# cyberspace-1-ram-rom-card.net
KiCad netlist of a schematic drawn in EAGLE
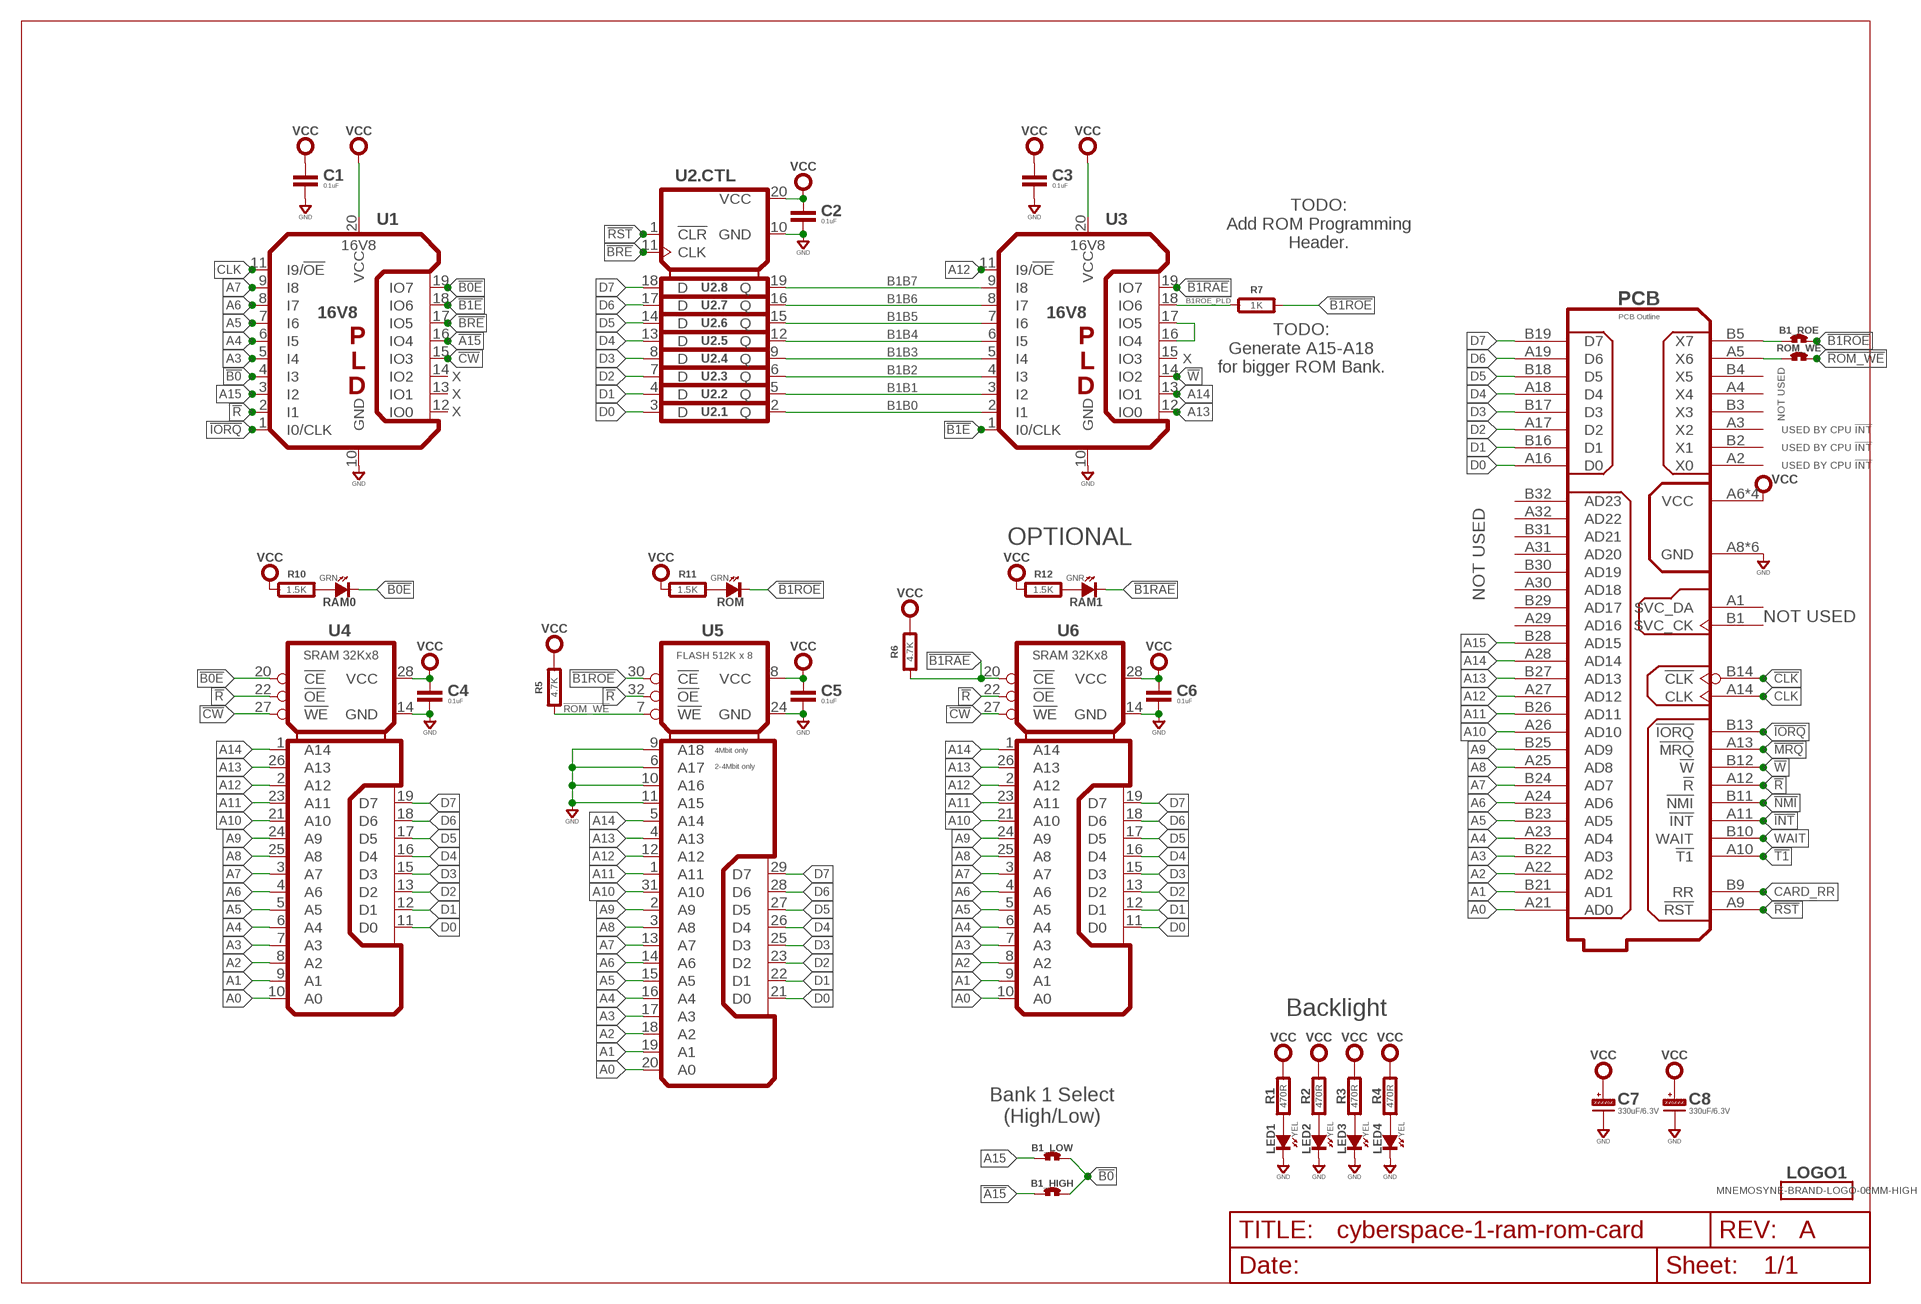
[diagram p0: schematic, sheet 1]

(export (version "E")
  (design (tool "Eeschema 10.0.6"))
  (components
    (comp (ref "B1_HIGH")
      (value "SOLDER_JUMPER-60MIL-RND")
      (footprint "eagle-import:SOLDER_JUMP_60MIL_RND")
      (libsource (lib "eagle-import") (part "SOLDER_JUMPER-60MIL-RND"))
    )
    (comp (ref "B1_LOW")
      (value "SOLDER_JUMPER-60MIL-RND")
      (footprint "eagle-import:SOLDER_JUMP_60MIL_RND")
      (libsource (lib "eagle-import") (part "SOLDER_JUMPER-60MIL-RND"))
    )
    (comp (ref "B1_ROE")
      (value "SOLDER_JUMPER-60MIL-RND")
      (footprint "eagle-import:SOLDER_JUMP_60MIL_RND")
      (libsource (lib "eagle-import") (part "SOLDER_JUMPER-60MIL-RND"))
    )
    (comp (ref "C1")
      (value "0.1uF")
      (footprint "eagle-import:0603-CAP")
      (libsource (lib "eagle-import") (part "CAPACITOR0603"))
    )
    (comp (ref "C2")
      (value "0.1uF")
      (footprint "eagle-import:0603-CAP")
      (libsource (lib "eagle-import") (part "CAPACITOR0603"))
    )
    (comp (ref "C3")
      (value "0.1uF")
      (footprint "eagle-import:0603-CAP")
      (libsource (lib "eagle-import") (part "CAPACITOR0603"))
    )
    (comp (ref "C4")
      (value "0.1uF")
      (footprint "eagle-import:0603-CAP")
      (libsource (lib "eagle-import") (part "CAPACITOR0603"))
    )
    (comp (ref "C5")
      (value "0.1uF")
      (footprint "eagle-import:0603-CAP")
      (libsource (lib "eagle-import") (part "CAPACITOR0603"))
    )
    (comp (ref "C6")
      (value "0.1uF")
      (footprint "eagle-import:0603-CAP")
      (libsource (lib "eagle-import") (part "CAPACITOR0603"))
    )
    (comp (ref "C7")
      (value "330uF/6.3V")
      (footprint "eagle-import:CAP_ALUM_SMT_6.3")
      (libsource (lib "eagle-import") (part "CAPACITOR_POL-ALUM-SMT-6.3"))
    )
    (comp (ref "C8")
      (value "330uF/6.3V")
      (footprint "eagle-import:CAP_ALUM_SMT_6.3")
      (libsource (lib "eagle-import") (part "CAPACITOR_POL-ALUM-SMT-6.3"))
    )
    (comp (ref "LED1")
      (value "YEL")
      (footprint "eagle-import:SMD_0603")
      (libsource (lib "eagle-import") (part "SMT0603"))
    )
    (comp (ref "LED2")
      (value "YEL")
      (footprint "eagle-import:SMD_0603")
      (libsource (lib "eagle-import") (part "SMT0603"))
    )
    (comp (ref "LED3")
      (value "YEL")
      (footprint "eagle-import:SMD_0603")
      (libsource (lib "eagle-import") (part "SMT0603"))
    )
    (comp (ref "LED4")
      (value "YEL")
      (footprint "eagle-import:SMD_0603")
      (libsource (lib "eagle-import") (part "SMT0603"))
    )
    (comp (ref "LOGO1")
      (value "MNEMOSYNE-BRAND-LOGO-06MM-HIGH")
      (footprint "eagle-import:MNEMOSYNE-06MM")
      (libsource (lib "eagle-import") (part "MNEMOSYNE-BRAND-LOGO-06MM-HIGH"))
    )
    (comp (ref "PCB")
      (value "PCB Outline")
      (footprint "eagle-import:CYBERSPACE-CARD-TYPE-1A")
      (libsource (lib "eagle-import") (part "CYBERSPACE-1-CARD-1A"))
    )
    (comp (ref "R1")
      (value "470R")
      (footprint "eagle-import:0603-RES")
      (libsource (lib "eagle-import") (part "RESISTOR0603"))
    )
    (comp (ref "R2")
      (value "470R")
      (footprint "eagle-import:0603-RES")
      (libsource (lib "eagle-import") (part "RESISTOR0603"))
    )
    (comp (ref "R3")
      (value "470R")
      (footprint "eagle-import:0603-RES")
      (libsource (lib "eagle-import") (part "RESISTOR0603"))
    )
    (comp (ref "R4")
      (value "470R")
      (footprint "eagle-import:0603-RES")
      (libsource (lib "eagle-import") (part "RESISTOR0603"))
    )
    (comp (ref "R5")
      (value "4.7K")
      (footprint "eagle-import:0603-RES")
      (libsource (lib "eagle-import") (part "RESISTOR0603"))
    )
    (comp (ref "R6")
      (value "4.7K")
      (footprint "eagle-import:0603-RES")
      (libsource (lib "eagle-import") (part "RESISTOR0603"))
    )
    (comp (ref "R7")
      (value "1K")
      (footprint "eagle-import:0603-RES")
      (libsource (lib "eagle-import") (part "RESISTOR0603"))
    )
    (comp (ref "R10")
      (value "1.5K")
      (footprint "eagle-import:0603-RES")
      (libsource (lib "eagle-import") (part "RESISTOR0603"))
    )
    (comp (ref "R11")
      (value "1.5K")
      (footprint "eagle-import:0603-RES")
      (libsource (lib "eagle-import") (part "RESISTOR0603"))
    )
    (comp (ref "R12")
      (value "1.5K")
      (footprint "eagle-import:0603-RES")
      (libsource (lib "eagle-import") (part "RESISTOR0603"))
    )
    (comp (ref "RAM0")
      (value "GRN")
      (footprint "eagle-import:SMD_0603")
      (libsource (lib "eagle-import") (part "SMT0603"))
    )
    (comp (ref "RAM1")
      (value "GNR")
      (footprint "eagle-import:SMD_0603")
      (libsource (lib "eagle-import") (part "SMT0603"))
    )
    (comp (ref "ROM")
      (value "GRN")
      (footprint "eagle-import:SMD_0603")
      (libsource (lib "eagle-import") (part "SMT0603"))
    )
    (comp (ref "ROM_WE")
      (value "SOLDER_JUMPER-60MIL-RND")
      (footprint "eagle-import:SOLDER_JUMP_60MIL_RND")
      (libsource (lib "eagle-import") (part "SOLDER_JUMPER-60MIL-RND"))
    )
    (comp (ref "U1")
      (value "16V8")
      (footprint "eagle-import:SOP20")
      (fields (field (name "MFR") "Atmel") (field (name "MPN") "AF16V8B15SU"))
      (libsource (lib "eagle-import") (part "16V8-SOIC"))
    )
    (comp (ref "U2")
      (value "74AHCT273NS")
      (footprint "eagle-import:SO20")
      (libsource (lib "eagle-import") (part "74273?NSAHCT"))
    )
    (comp (ref "U3")
      (value "16V8")
      (footprint "eagle-import:SOP20")
      (fields (field (name "MFR") "Atmel") (field (name "MPN") "AF16V8B15SU"))
      (libsource (lib "eagle-import") (part "16V8-SOIC"))
    )
    (comp (ref "U4")
      (value "SRAM 32Kx8")
      (footprint "eagle-import:SOP28-330W")
      (fields (field (name "MFR") "ISSI") (field (name "MPN") "IS62C256AL-45UL"))
      (libsource (lib "eagle-import") (part "62256ULC"))
    )
    (comp (ref "U5")
      (value "FLASH 512K x 8")
      (footprint "eagle-import:TSOP32-14X8MM")
      (fields (field (name "MFR") "Microchip") (field (name "MPN") "SST39SF040-70-4C-Wxx"))
      (libsource (lib "eagle-import") (part "FLASH_512KX8-512K-TSOP"))
    )
    (comp (ref "U6")
      (value "SRAM 32Kx8")
      (footprint "eagle-import:SOP28-330W")
      (fields (field (name "MFR") "ISSI") (field (name "MPN") "IS62C256AL-45UL"))
      (libsource (lib "eagle-import") (part "62256ULC"))
    )
  )
  (nets
    (net (code "1") (name "/B1B0") (class "Default")
      (node (ref "U2") (pin "2") (pinfunction "Q_2") (pintype "output"))
      (node (ref "U3") (pin "2") (pinfunction "I1_2") (pintype "bidirectional"))
    )
    (net (code "2") (name "/B1B1") (class "Default")
      (node (ref "U2") (pin "5") (pinfunction "Q_5") (pintype "output"))
      (node (ref "U3") (pin "3") (pinfunction "I2_3") (pintype "bidirectional"))
    )
    (net (code "3") (name "/B1B2") (class "Default")
      (node (ref "U2") (pin "6") (pinfunction "Q_6") (pintype "output"))
      (node (ref "U3") (pin "4") (pinfunction "I3_4") (pintype "bidirectional"))
    )
    (net (code "4") (name "/B1B3") (class "Default")
      (node (ref "U2") (pin "9") (pinfunction "Q_9") (pintype "output"))
      (node (ref "U3") (pin "5") (pinfunction "I4_5") (pintype "bidirectional"))
    )
    (net (code "5") (name "/B1B4") (class "Default")
      (node (ref "U2") (pin "12") (pinfunction "Q_12") (pintype "output"))
      (node (ref "U3") (pin "6") (pinfunction "I5_6") (pintype "bidirectional"))
    )
    (net (code "6") (name "/B1B5") (class "Default")
      (node (ref "U2") (pin "15") (pinfunction "Q_15") (pintype "output"))
      (node (ref "U3") (pin "7") (pinfunction "I6_7") (pintype "bidirectional"))
    )
    (net (code "7") (name "/B1B6") (class "Default")
      (node (ref "U2") (pin "16") (pinfunction "Q_16") (pintype "output"))
      (node (ref "U3") (pin "8") (pinfunction "I7_8") (pintype "bidirectional"))
    )
    (net (code "8") (name "/B1B7") (class "Default")
      (node (ref "U2") (pin "19") (pinfunction "Q_19") (pintype "output"))
      (node (ref "U3") (pin "9") (pinfunction "I8_9") (pintype "bidirectional"))
    )
    (net (code "9") (name "/~{A15}") (class "Default")
      (node (ref "B1_HIGH") (pin "1") (pinfunction "P$1_1") (pintype "passive"))
      (node (ref "U1") (pin "16") (pinfunction "IO4_16") (pintype "bidirectional"))
    )
    (net (code "10") (name "/~{B0E}") (class "Default")
      (node (ref "RAM0") (pin "K") (pinfunction "C_K") (pintype "passive"))
      (node (ref "U1") (pin "19") (pinfunction "IO7_19") (pintype "bidirectional"))
      (node (ref "U4") (pin "20") (pinfunction "~{CE}_20") (pintype "input"))
    )
    (net (code "11") (name "/~{B0}") (class "Default")
      (node (ref "B1_HIGH") (pin "2") (pinfunction "P$2_2") (pintype "passive"))
      (node (ref "B1_LOW") (pin "2") (pinfunction "P$2_2") (pintype "passive"))
      (node (ref "U1") (pin "4") (pinfunction "I3_4") (pintype "bidirectional"))
    )
    (net (code "12") (name "/~{B1E}") (class "Default")
      (node (ref "U1") (pin "18") (pinfunction "IO6_18") (pintype "bidirectional"))
      (node (ref "U3") (pin "1") (pinfunction "I0/CLK_1") (pintype "bidirectional"))
    )
    (net (code "13") (name "/~{B1RAE}") (class "Default")
      (node (ref "R6") (pin "1") (pinfunction "1_1") (pintype "passive"))
      (node (ref "RAM1") (pin "K") (pinfunction "C_K") (pintype "passive"))
      (node (ref "U3") (pin "19") (pinfunction "IO7_19") (pintype "bidirectional"))
      (node (ref "U6") (pin "20") (pinfunction "~{CE}_20") (pintype "input"))
    )
    (net (code "14") (name "/~{B1ROE_PLD}") (class "Default")
      (node (ref "R7") (pin "1") (pinfunction "1_1") (pintype "passive"))
      (node (ref "U3") (pin "18") (pinfunction "IO6_18") (pintype "bidirectional"))
    )
    (net (code "15") (name "/~{B1ROE}") (class "Default")
      (node (ref "B1_ROE") (pin "2") (pinfunction "P$2_2") (pintype "passive"))
      (node (ref "R7") (pin "2") (pinfunction "2_2") (pintype "passive"))
      (node (ref "ROM") (pin "K") (pinfunction "C_K") (pintype "passive"))
      (node (ref "U5") (pin "30") (pinfunction "~{CE}_30") (pintype "input"))
    )
    (net (code "16") (name "/~{BRE}") (class "Default")
      (node (ref "U1") (pin "17") (pinfunction "IO5_17") (pintype "bidirectional"))
      (node (ref "U2") (pin "11") (pinfunction "CLK_11") (pintype "input"))
    )
    (net (code "17") (name "/~{CLK}") (class "Default")
      (node (ref "PCB") (pin "B14") (pinfunction "~{CLK}_B14") (pintype "bidirectional"))
    )
    (net (code "18") (name "/~{CW}") (class "Default")
      (node (ref "U1") (pin "15") (pinfunction "IO3_15") (pintype "bidirectional"))
      (node (ref "U4") (pin "27") (pinfunction "~{WE}_27") (pintype "input"))
      (node (ref "U6") (pin "27") (pinfunction "~{WE}_27") (pintype "input"))
    )
    (net (code "19") (name "/~{INT}") (class "Default")
      (node (ref "PCB") (pin "A11") (pinfunction "~{INT}_A11") (pintype "bidirectional"))
    )
    (net (code "20") (name "/~{IORQ}") (class "Default")
      (node (ref "PCB") (pin "B13") (pinfunction "~{IORQ}_B13") (pintype "bidirectional"))
      (node (ref "U1") (pin "1") (pinfunction "I0/CLK_1") (pintype "bidirectional"))
    )
    (net (code "21") (name "/~{MRQ}") (class "Default")
      (node (ref "PCB") (pin "A13") (pinfunction "~{MRQ}_A13") (pintype "bidirectional"))
    )
    (net (code "22") (name "/~{NMI}") (class "Default")
      (node (ref "PCB") (pin "B11") (pinfunction "~{NMI}_B11") (pintype "bidirectional"))
    )
    (net (code "23") (name "/~{ROM_WE}") (class "Default")
      (node (ref "R5") (pin "1") (pinfunction "1_1") (pintype "passive"))
      (node (ref "ROM_WE") (pin "2") (pinfunction "P$2_2") (pintype "passive"))
      (node (ref "U5") (pin "7") (pinfunction "~{WE}_7") (pintype "input"))
    )
    (net (code "24") (name "/~{RST}") (class "Default")
      (node (ref "PCB") (pin "A9") (pinfunction "~{RST}_A9") (pintype "bidirectional"))
      (node (ref "U2") (pin "1") (pinfunction "~{CLR}_1") (pintype "input"))
    )
    (net (code "25") (name "/~{R}") (class "Default")
      (node (ref "PCB") (pin "A12") (pinfunction "~{R}_A12") (pintype "bidirectional"))
      (node (ref "U1") (pin "2") (pinfunction "I1_2") (pintype "bidirectional"))
      (node (ref "U4") (pin "22") (pinfunction "~{OE}_22") (pintype "input"))
      (node (ref "U5") (pin "32") (pinfunction "~{OE}_32") (pintype "input"))
      (node (ref "U6") (pin "22") (pinfunction "~{OE}_22") (pintype "input"))
    )
    (net (code "26") (name "/~{T1}") (class "Default")
      (node (ref "PCB") (pin "A10") (pinfunction "~{T1}_A10") (pintype "bidirectional"))
    )
    (net (code "27") (name "/~{W}") (class "Default")
      (node (ref "PCB") (pin "B12") (pinfunction "~{W}_B12") (pintype "bidirectional"))
      (node (ref "U3") (pin "14") (pinfunction "IO2_14") (pintype "bidirectional"))
    )
    (net (code "28") (name "A0") (class "Default")
      (node (ref "PCB") (pin "A21") (pinfunction "AD0_A21") (pintype "bidirectional"))
      (node (ref "U4") (pin "10") (pinfunction "A0_10") (pintype "input"))
      (node (ref "U5") (pin "20") (pinfunction "A0_20") (pintype "input"))
      (node (ref "U6") (pin "10") (pinfunction "A0_10") (pintype "input"))
    )
    (net (code "29") (name "A1") (class "Default")
      (node (ref "PCB") (pin "B21") (pinfunction "AD1_B21") (pintype "bidirectional"))
      (node (ref "U4") (pin "9") (pinfunction "A1_9") (pintype "input"))
      (node (ref "U5") (pin "19") (pinfunction "A1_19") (pintype "input"))
      (node (ref "U6") (pin "9") (pinfunction "A1_9") (pintype "input"))
    )
    (net (code "30") (name "A2") (class "Default")
      (node (ref "PCB") (pin "A22") (pinfunction "AD2_A22") (pintype "bidirectional"))
      (node (ref "U4") (pin "8") (pinfunction "A2_8") (pintype "input"))
      (node (ref "U5") (pin "18") (pinfunction "A2_18") (pintype "input"))
      (node (ref "U6") (pin "8") (pinfunction "A2_8") (pintype "input"))
    )
    (net (code "31") (name "A3") (class "Default")
      (node (ref "PCB") (pin "B22") (pinfunction "AD3_B22") (pintype "bidirectional"))
      (node (ref "U1") (pin "5") (pinfunction "I4_5") (pintype "bidirectional"))
      (node (ref "U4") (pin "7") (pinfunction "A3_7") (pintype "input"))
      (node (ref "U5") (pin "17") (pinfunction "A3_17") (pintype "input"))
      (node (ref "U6") (pin "7") (pinfunction "A3_7") (pintype "input"))
    )
    (net (code "32") (name "A4") (class "Default")
      (node (ref "PCB") (pin "A23") (pinfunction "AD4_A23") (pintype "bidirectional"))
      (node (ref "U1") (pin "6") (pinfunction "I5_6") (pintype "bidirectional"))
      (node (ref "U4") (pin "6") (pinfunction "A4_6") (pintype "input"))
      (node (ref "U5") (pin "16") (pinfunction "A4_16") (pintype "input"))
      (node (ref "U6") (pin "6") (pinfunction "A4_6") (pintype "input"))
    )
    (net (code "33") (name "A5") (class "Default")
      (node (ref "PCB") (pin "B23") (pinfunction "AD5_B23") (pintype "bidirectional"))
      (node (ref "U1") (pin "7") (pinfunction "I6_7") (pintype "bidirectional"))
      (node (ref "U4") (pin "5") (pinfunction "A5_5") (pintype "input"))
      (node (ref "U5") (pin "15") (pinfunction "A5_15") (pintype "input"))
      (node (ref "U6") (pin "5") (pinfunction "A5_5") (pintype "input"))
    )
    (net (code "34") (name "A6") (class "Default")
      (node (ref "PCB") (pin "A24") (pinfunction "AD6_A24") (pintype "bidirectional"))
      (node (ref "U1") (pin "8") (pinfunction "I7_8") (pintype "bidirectional"))
      (node (ref "U4") (pin "4") (pinfunction "A6_4") (pintype "input"))
      (node (ref "U5") (pin "14") (pinfunction "A6_14") (pintype "input"))
      (node (ref "U6") (pin "4") (pinfunction "A6_4") (pintype "input"))
    )
    (net (code "35") (name "A7") (class "Default")
      (node (ref "PCB") (pin "B24") (pinfunction "AD7_B24") (pintype "bidirectional"))
      (node (ref "U1") (pin "9") (pinfunction "I8_9") (pintype "bidirectional"))
      (node (ref "U4") (pin "3") (pinfunction "A7_3") (pintype "input"))
      (node (ref "U5") (pin "13") (pinfunction "A7_13") (pintype "input"))
      (node (ref "U6") (pin "3") (pinfunction "A7_3") (pintype "input"))
    )
    (net (code "36") (name "A8") (class "Default")
      (node (ref "PCB") (pin "A25") (pinfunction "AD8_A25") (pintype "bidirectional"))
      (node (ref "U4") (pin "25") (pinfunction "A8_25") (pintype "input"))
      (node (ref "U5") (pin "3") (pinfunction "A8_3") (pintype "input"))
      (node (ref "U6") (pin "25") (pinfunction "A8_25") (pintype "input"))
    )
    (net (code "37") (name "A9") (class "Default")
      (node (ref "PCB") (pin "B25") (pinfunction "AD9_B25") (pintype "bidirectional"))
      (node (ref "U4") (pin "24") (pinfunction "A9_24") (pintype "input"))
      (node (ref "U5") (pin "2") (pinfunction "A9_2") (pintype "input"))
      (node (ref "U6") (pin "24") (pinfunction "A9_24") (pintype "input"))
    )
    (net (code "38") (name "A10") (class "Default")
      (node (ref "PCB") (pin "A26") (pinfunction "AD10_A26") (pintype "bidirectional"))
      (node (ref "U4") (pin "21") (pinfunction "A10_21") (pintype "input"))
      (node (ref "U5") (pin "31") (pinfunction "A10_31") (pintype "input"))
      (node (ref "U6") (pin "21") (pinfunction "A10_21") (pintype "input"))
    )
    (net (code "39") (name "A11") (class "Default")
      (node (ref "PCB") (pin "B26") (pinfunction "AD11_B26") (pintype "bidirectional"))
      (node (ref "U4") (pin "23") (pinfunction "A11_23") (pintype "input"))
      (node (ref "U5") (pin "1") (pinfunction "A11_1") (pintype "input"))
      (node (ref "U6") (pin "23") (pinfunction "A11_23") (pintype "input"))
    )
    (net (code "40") (name "A12") (class "Default")
      (node (ref "PCB") (pin "A27") (pinfunction "AD12_A27") (pintype "bidirectional"))
      (node (ref "U3") (pin "11") (pinfunction "I9/~{OE}_11") (pintype "bidirectional"))
      (node (ref "U4") (pin "2") (pinfunction "A12_2") (pintype "input"))
      (node (ref "U5") (pin "12") (pinfunction "A12_12") (pintype "input"))
      (node (ref "U6") (pin "2") (pinfunction "A12_2") (pintype "input"))
    )
    (net (code "41") (name "A13") (class "Default")
      (node (ref "PCB") (pin "B27") (pinfunction "AD13_B27") (pintype "bidirectional"))
      (node (ref "U3") (pin "12") (pinfunction "IO0_12") (pintype "bidirectional"))
      (node (ref "U4") (pin "26") (pinfunction "A13_26") (pintype "input"))
      (node (ref "U5") (pin "4") (pinfunction "A13_4") (pintype "input"))
      (node (ref "U6") (pin "26") (pinfunction "A13_26") (pintype "input"))
    )
    (net (code "42") (name "A14") (class "Default")
      (node (ref "PCB") (pin "A28") (pinfunction "AD14_A28") (pintype "bidirectional"))
      (node (ref "U3") (pin "13") (pinfunction "IO1_13") (pintype "bidirectional"))
      (node (ref "U4") (pin "1") (pinfunction "A14_1") (pintype "input"))
      (node (ref "U5") (pin "5") (pinfunction "A14_5") (pintype "input"))
      (node (ref "U6") (pin "1") (pinfunction "A14_1") (pintype "input"))
    )
    (net (code "43") (name "A15") (class "Default")
      (node (ref "B1_LOW") (pin "1") (pinfunction "P$1_1") (pintype "passive"))
      (node (ref "PCB") (pin "B28") (pinfunction "AD15_B28") (pintype "bidirectional"))
      (node (ref "U1") (pin "3") (pinfunction "I2_3") (pintype "bidirectional"))
    )
    (net (code "44") (name "CARD_RR") (class "Default")
      (node (ref "PCB") (pin "B9") (pinfunction "RR_B9") (pintype "bidirectional"))
    )
    (net (code "45") (name "CLK") (class "Default")
      (node (ref "PCB") (pin "A14") (pinfunction "CLK_A14") (pintype "bidirectional"))
      (node (ref "U1") (pin "11") (pinfunction "I9/~{OE}_11") (pintype "bidirectional"))
    )
    (net (code "46") (name "D0") (class "Default")
      (node (ref "PCB") (pin "A16") (pinfunction "D0_A16") (pintype "bidirectional"))
      (node (ref "U2") (pin "3") (pinfunction "D_3") (pintype "input"))
      (node (ref "U4") (pin "11") (pinfunction "D0_11") (pintype "bidirectional"))
      (node (ref "U5") (pin "21") (pinfunction "D0_21") (pintype "bidirectional"))
      (node (ref "U6") (pin "11") (pinfunction "D0_11") (pintype "bidirectional"))
    )
    (net (code "47") (name "D1") (class "Default")
      (node (ref "PCB") (pin "B16") (pinfunction "D1_B16") (pintype "bidirectional"))
      (node (ref "U2") (pin "4") (pinfunction "D_4") (pintype "input"))
      (node (ref "U4") (pin "12") (pinfunction "D1_12") (pintype "bidirectional"))
      (node (ref "U5") (pin "22") (pinfunction "D1_22") (pintype "bidirectional"))
      (node (ref "U6") (pin "12") (pinfunction "D1_12") (pintype "bidirectional"))
    )
    (net (code "48") (name "D2") (class "Default")
      (node (ref "PCB") (pin "A17") (pinfunction "D2_A17") (pintype "bidirectional"))
      (node (ref "U2") (pin "7") (pinfunction "D_7") (pintype "input"))
      (node (ref "U4") (pin "13") (pinfunction "D2_13") (pintype "bidirectional"))
      (node (ref "U5") (pin "23") (pinfunction "D2_23") (pintype "bidirectional"))
      (node (ref "U6") (pin "13") (pinfunction "D2_13") (pintype "bidirectional"))
    )
    (net (code "49") (name "D3") (class "Default")
      (node (ref "PCB") (pin "B17") (pinfunction "D3_B17") (pintype "bidirectional"))
      (node (ref "U2") (pin "8") (pinfunction "D_8") (pintype "input"))
      (node (ref "U4") (pin "15") (pinfunction "D3_15") (pintype "bidirectional"))
      (node (ref "U5") (pin "25") (pinfunction "D3_25") (pintype "bidirectional"))
      (node (ref "U6") (pin "15") (pinfunction "D3_15") (pintype "bidirectional"))
    )
    (net (code "50") (name "D4") (class "Default")
      (node (ref "PCB") (pin "A18") (pinfunction "D4_A18") (pintype "bidirectional"))
      (node (ref "U2") (pin "13") (pinfunction "D_13") (pintype "input"))
      (node (ref "U4") (pin "16") (pinfunction "D4_16") (pintype "bidirectional"))
      (node (ref "U5") (pin "26") (pinfunction "D4_26") (pintype "bidirectional"))
      (node (ref "U6") (pin "16") (pinfunction "D4_16") (pintype "bidirectional"))
    )
    (net (code "51") (name "D5") (class "Default")
      (node (ref "PCB") (pin "B18") (pinfunction "D5_B18") (pintype "bidirectional"))
      (node (ref "U2") (pin "14") (pinfunction "D_14") (pintype "input"))
      (node (ref "U4") (pin "17") (pinfunction "D5_17") (pintype "bidirectional"))
      (node (ref "U5") (pin "27") (pinfunction "D5_27") (pintype "bidirectional"))
      (node (ref "U6") (pin "17") (pinfunction "D5_17") (pintype "bidirectional"))
    )
    (net (code "52") (name "D6") (class "Default")
      (node (ref "PCB") (pin "A19") (pinfunction "D6_A19") (pintype "bidirectional"))
      (node (ref "U2") (pin "17") (pinfunction "D_17") (pintype "input"))
      (node (ref "U4") (pin "18") (pinfunction "D6_18") (pintype "bidirectional"))
      (node (ref "U5") (pin "28") (pinfunction "D6_28") (pintype "bidirectional"))
      (node (ref "U6") (pin "18") (pinfunction "D6_18") (pintype "bidirectional"))
    )
    (net (code "53") (name "D7") (class "Default")
      (node (ref "PCB") (pin "B19") (pinfunction "D7_B19") (pintype "bidirectional"))
      (node (ref "U2") (pin "18") (pinfunction "D_18") (pintype "input"))
      (node (ref "U4") (pin "19") (pinfunction "D7_19") (pintype "bidirectional"))
      (node (ref "U5") (pin "29") (pinfunction "D7_29") (pintype "bidirectional"))
      (node (ref "U6") (pin "19") (pinfunction "D7_19") (pintype "bidirectional"))
    )
    (net (code "54") (name "GND") (class "Default")
      (node (ref "C1") (pin "2") (pinfunction "2_2") (pintype "passive"))
      (node (ref "C2") (pin "2") (pinfunction "2_2") (pintype "passive"))
      (node (ref "C3") (pin "2") (pinfunction "2_2") (pintype "passive"))
      (node (ref "C4") (pin "2") (pinfunction "2_2") (pintype "passive"))
      (node (ref "C5") (pin "2") (pinfunction "2_2") (pintype "passive"))
      (node (ref "C6") (pin "2") (pinfunction "2_2") (pintype "passive"))
      (node (ref "C7") (pin "-") (pinfunction "N_-") (pintype "bidirectional"))
      (node (ref "C8") (pin "-") (pinfunction "N_-") (pintype "bidirectional"))
      (node (ref "LED1") (pin "K") (pinfunction "C_K") (pintype "passive"))
      (node (ref "LED2") (pin "K") (pinfunction "C_K") (pintype "passive"))
      (node (ref "LED3") (pin "K") (pinfunction "C_K") (pintype "passive"))
      (node (ref "LED4") (pin "K") (pinfunction "C_K") (pintype "passive"))
      (node (ref "PCB") (pin "A15") (pinfunction "GND_A15") (pintype "power_in"))
      (node (ref "PCB") (pin "A20") (pinfunction "GND_A20") (pintype "power_in"))
      (node (ref "PCB") (pin "A8") (pinfunction "GND_A8") (pintype "power_in"))
      (node (ref "PCB") (pin "B15") (pinfunction "GND_B15") (pintype "power_in"))
      (node (ref "PCB") (pin "B20") (pinfunction "GND_B20") (pintype "power_in"))
      (node (ref "PCB") (pin "B8") (pinfunction "GND_B8") (pintype "power_in"))
      (node (ref "U1") (pin "10") (pinfunction "GND_10") (pintype "bidirectional"))
      (node (ref "U2") (pin "10") (pinfunction "GND_10") (pintype "power_in"))
      (node (ref "U3") (pin "10") (pinfunction "GND_10") (pintype "bidirectional"))
      (node (ref "U4") (pin "14") (pinfunction "GND_14") (pintype "power_in"))
      (node (ref "U5") (pin "10") (pinfunction "A16_10") (pintype "input"))
      (node (ref "U5") (pin "11") (pinfunction "A15_11") (pintype "input"))
      (node (ref "U5") (pin "24") (pinfunction "GND_24") (pintype "power_in"))
      (node (ref "U5") (pin "6") (pinfunction "A17_6") (pintype "input"))
      (node (ref "U5") (pin "9") (pinfunction "A18_9") (pintype "input"))
      (node (ref "U6") (pin "14") (pinfunction "GND_14") (pintype "power_in"))
    )
    (net (code "55") (name "Net-(B1_ROE-P$1)") (class "Default")
      (node (ref "B1_ROE") (pin "1") (pinfunction "P$1_1") (pintype "passive"))
      (node (ref "PCB") (pin "B5") (pinfunction "X7_B5") (pintype "bidirectional"))
    )
    (net (code "56") (name "Net-(LED1-PadA)") (class "Default")
      (node (ref "LED1") (pin "A") (pinfunction "A_A") (pintype "passive"))
      (node (ref "R1") (pin "1") (pinfunction "1_1") (pintype "passive"))
    )
    (net (code "57") (name "Net-(LED2-PadA)") (class "Default")
      (node (ref "LED2") (pin "A") (pinfunction "A_A") (pintype "passive"))
      (node (ref "R2") (pin "1") (pinfunction "1_1") (pintype "passive"))
    )
    (net (code "58") (name "Net-(LED3-PadA)") (class "Default")
      (node (ref "LED3") (pin "A") (pinfunction "A_A") (pintype "passive"))
      (node (ref "R3") (pin "1") (pinfunction "1_1") (pintype "passive"))
    )
    (net (code "59") (name "Net-(LED4-PadA)") (class "Default")
      (node (ref "LED4") (pin "A") (pinfunction "A_A") (pintype "passive"))
      (node (ref "R4") (pin "1") (pinfunction "1_1") (pintype "passive"))
    )
    (net (code "60") (name "Net-(PCB-X6)") (class "Default")
      (node (ref "PCB") (pin "A5") (pinfunction "X6_A5") (pintype "bidirectional"))
      (node (ref "ROM_WE") (pin "1") (pinfunction "P$1_1") (pintype "passive"))
    )
    (net (code "61") (name "Net-(R10-Pad2)") (class "Default")
      (node (ref "R10") (pin "2") (pinfunction "2_2") (pintype "passive"))
      (node (ref "RAM0") (pin "A") (pinfunction "A_A") (pintype "passive"))
    )
    (net (code "62") (name "Net-(R11-Pad2)") (class "Default")
      (node (ref "R11") (pin "2") (pinfunction "2_2") (pintype "passive"))
      (node (ref "ROM") (pin "A") (pinfunction "A_A") (pintype "passive"))
    )
    (net (code "63") (name "Net-(R12-Pad2)") (class "Default")
      (node (ref "R12") (pin "2") (pinfunction "2_2") (pintype "passive"))
      (node (ref "RAM1") (pin "A") (pinfunction "A_A") (pintype "passive"))
    )
    (net (code "64") (name "Net-(U3-IO4)") (class "Default")
      (node (ref "U3") (pin "16") (pinfunction "IO4_16") (pintype "bidirectional"))
      (node (ref "U3") (pin "17") (pinfunction "IO5_17") (pintype "bidirectional"))
    )
    (net (code "65") (name "VCC") (class "Default")
      (node (ref "C1") (pin "1") (pinfunction "1_1") (pintype "passive"))
      (node (ref "C2") (pin "1") (pinfunction "1_1") (pintype "passive"))
      (node (ref "C3") (pin "1") (pinfunction "1_1") (pintype "passive"))
      (node (ref "C4") (pin "1") (pinfunction "1_1") (pintype "passive"))
      (node (ref "C5") (pin "1") (pinfunction "1_1") (pintype "passive"))
      (node (ref "C6") (pin "1") (pinfunction "1_1") (pintype "passive"))
      (node (ref "C7") (pin "+") (pinfunction "P_+") (pintype "bidirectional"))
      (node (ref "C8") (pin "+") (pinfunction "P_+") (pintype "bidirectional"))
      (node (ref "PCB") (pin "A6") (pinfunction "VCC_A6") (pintype "power_in"))
      (node (ref "PCB") (pin "A7") (pinfunction "VCC_A7") (pintype "power_in"))
      (node (ref "PCB") (pin "B6") (pinfunction "VCC_B6") (pintype "power_in"))
      (node (ref "PCB") (pin "B7") (pinfunction "VCC_B7") (pintype "power_in"))
      (node (ref "R1") (pin "2") (pinfunction "2_2") (pintype "passive"))
      (node (ref "R10") (pin "1") (pinfunction "1_1") (pintype "passive"))
      (node (ref "R11") (pin "1") (pinfunction "1_1") (pintype "passive"))
      (node (ref "R12") (pin "1") (pinfunction "1_1") (pintype "passive"))
      (node (ref "R2") (pin "2") (pinfunction "2_2") (pintype "passive"))
      (node (ref "R3") (pin "2") (pinfunction "2_2") (pintype "passive"))
      (node (ref "R4") (pin "2") (pinfunction "2_2") (pintype "passive"))
      (node (ref "R5") (pin "2") (pinfunction "2_2") (pintype "passive"))
      (node (ref "R6") (pin "2") (pinfunction "2_2") (pintype "passive"))
      (node (ref "U1") (pin "20") (pinfunction "VCC_20") (pintype "bidirectional"))
      (node (ref "U2") (pin "20") (pinfunction "VCC_20") (pintype "power_in"))
      (node (ref "U3") (pin "20") (pinfunction "VCC_20") (pintype "bidirectional"))
      (node (ref "U4") (pin "28") (pinfunction "VCC_28") (pintype "power_in"))
      (node (ref "U5") (pin "8") (pinfunction "VCC_8") (pintype "power_in"))
      (node (ref "U6") (pin "28") (pinfunction "VCC_28") (pintype "power_in"))
    )
    (net (code "66") (name "WAIT") (class "Default")
      (node (ref "PCB") (pin "B10") (pinfunction "WAIT_B10") (pintype "bidirectional"))
    )
    (net (code "67") (name "unconnected-(PCB-AD16-PadA29)") (class "Default")
      (node (ref "PCB") (pin "A29") (pinfunction "AD16_A29") (pintype "bidirectional"))
    )
    (net (code "68") (name "unconnected-(PCB-AD17-PadB29)") (class "Default")
      (node (ref "PCB") (pin "B29") (pinfunction "AD17_B29") (pintype "bidirectional"))
    )
    (net (code "69") (name "unconnected-(PCB-AD18-PadA30)") (class "Default")
      (node (ref "PCB") (pin "A30") (pinfunction "AD18_A30") (pintype "bidirectional"))
    )
    (net (code "70") (name "unconnected-(PCB-AD19-PadB30)") (class "Default")
      (node (ref "PCB") (pin "B30") (pinfunction "AD19_B30") (pintype "bidirectional"))
    )
    (net (code "71") (name "unconnected-(PCB-AD20-PadA31)") (class "Default")
      (node (ref "PCB") (pin "A31") (pinfunction "AD20_A31") (pintype "bidirectional"))
    )
    (net (code "72") (name "unconnected-(PCB-AD21-PadB31)") (class "Default")
      (node (ref "PCB") (pin "B31") (pinfunction "AD21_B31") (pintype "bidirectional"))
    )
    (net (code "73") (name "unconnected-(PCB-AD22-PadA32)") (class "Default")
      (node (ref "PCB") (pin "A32") (pinfunction "AD22_A32") (pintype "bidirectional"))
    )
    (net (code "74") (name "unconnected-(PCB-AD23-PadB32)") (class "Default")
      (node (ref "PCB") (pin "B32") (pinfunction "AD23_B32") (pintype "bidirectional"))
    )
    (net (code "75") (name "unconnected-(PCB-SVC_CK-PadB1)") (class "Default")
      (node (ref "PCB") (pin "B1") (pinfunction "SVC_CK_B1") (pintype "bidirectional"))
    )
    (net (code "76") (name "unconnected-(PCB-SVC_DA-PadA1)") (class "Default")
      (node (ref "PCB") (pin "A1") (pinfunction "SVC_DA_A1") (pintype "bidirectional"))
    )
    (net (code "77") (name "unconnected-(PCB-X0-PadA2)") (class "Default")
      (node (ref "PCB") (pin "A2") (pinfunction "X0_A2") (pintype "bidirectional"))
    )
    (net (code "78") (name "unconnected-(PCB-X1-PadB2)") (class "Default")
      (node (ref "PCB") (pin "B2") (pinfunction "X1_B2") (pintype "bidirectional"))
    )
    (net (code "79") (name "unconnected-(PCB-X2-PadA3)") (class "Default")
      (node (ref "PCB") (pin "A3") (pinfunction "X2_A3") (pintype "bidirectional"))
    )
    (net (code "80") (name "unconnected-(PCB-X3-PadB3)") (class "Default")
      (node (ref "PCB") (pin "B3") (pinfunction "X3_B3") (pintype "bidirectional"))
    )
    (net (code "81") (name "unconnected-(PCB-X4-PadA4)") (class "Default")
      (node (ref "PCB") (pin "A4") (pinfunction "X4_A4") (pintype "bidirectional"))
    )
    (net (code "82") (name "unconnected-(PCB-X5-PadB4)") (class "Default")
      (node (ref "PCB") (pin "B4") (pinfunction "X5_B4") (pintype "bidirectional"))
    )
    (net (code "83") (name "unconnected-(U1-IO0-Pad12)") (class "Default")
      (node (ref "U1") (pin "12") (pinfunction "IO0_12") (pintype "bidirectional"))
    )
    (net (code "84") (name "unconnected-(U1-IO1-Pad13)") (class "Default")
      (node (ref "U1") (pin "13") (pinfunction "IO1_13") (pintype "bidirectional"))
    )
    (net (code "85") (name "unconnected-(U1-IO2-Pad14)") (class "Default")
      (node (ref "U1") (pin "14") (pinfunction "IO2_14") (pintype "bidirectional"))
    )
    (net (code "86") (name "unconnected-(U3-IO3-Pad15)") (class "Default")
      (node (ref "U3") (pin "15") (pinfunction "IO3_15") (pintype "bidirectional"))
    )
  )
)
